# NoMD.net
KiCad netlist of a schematic drawn in EAGLE
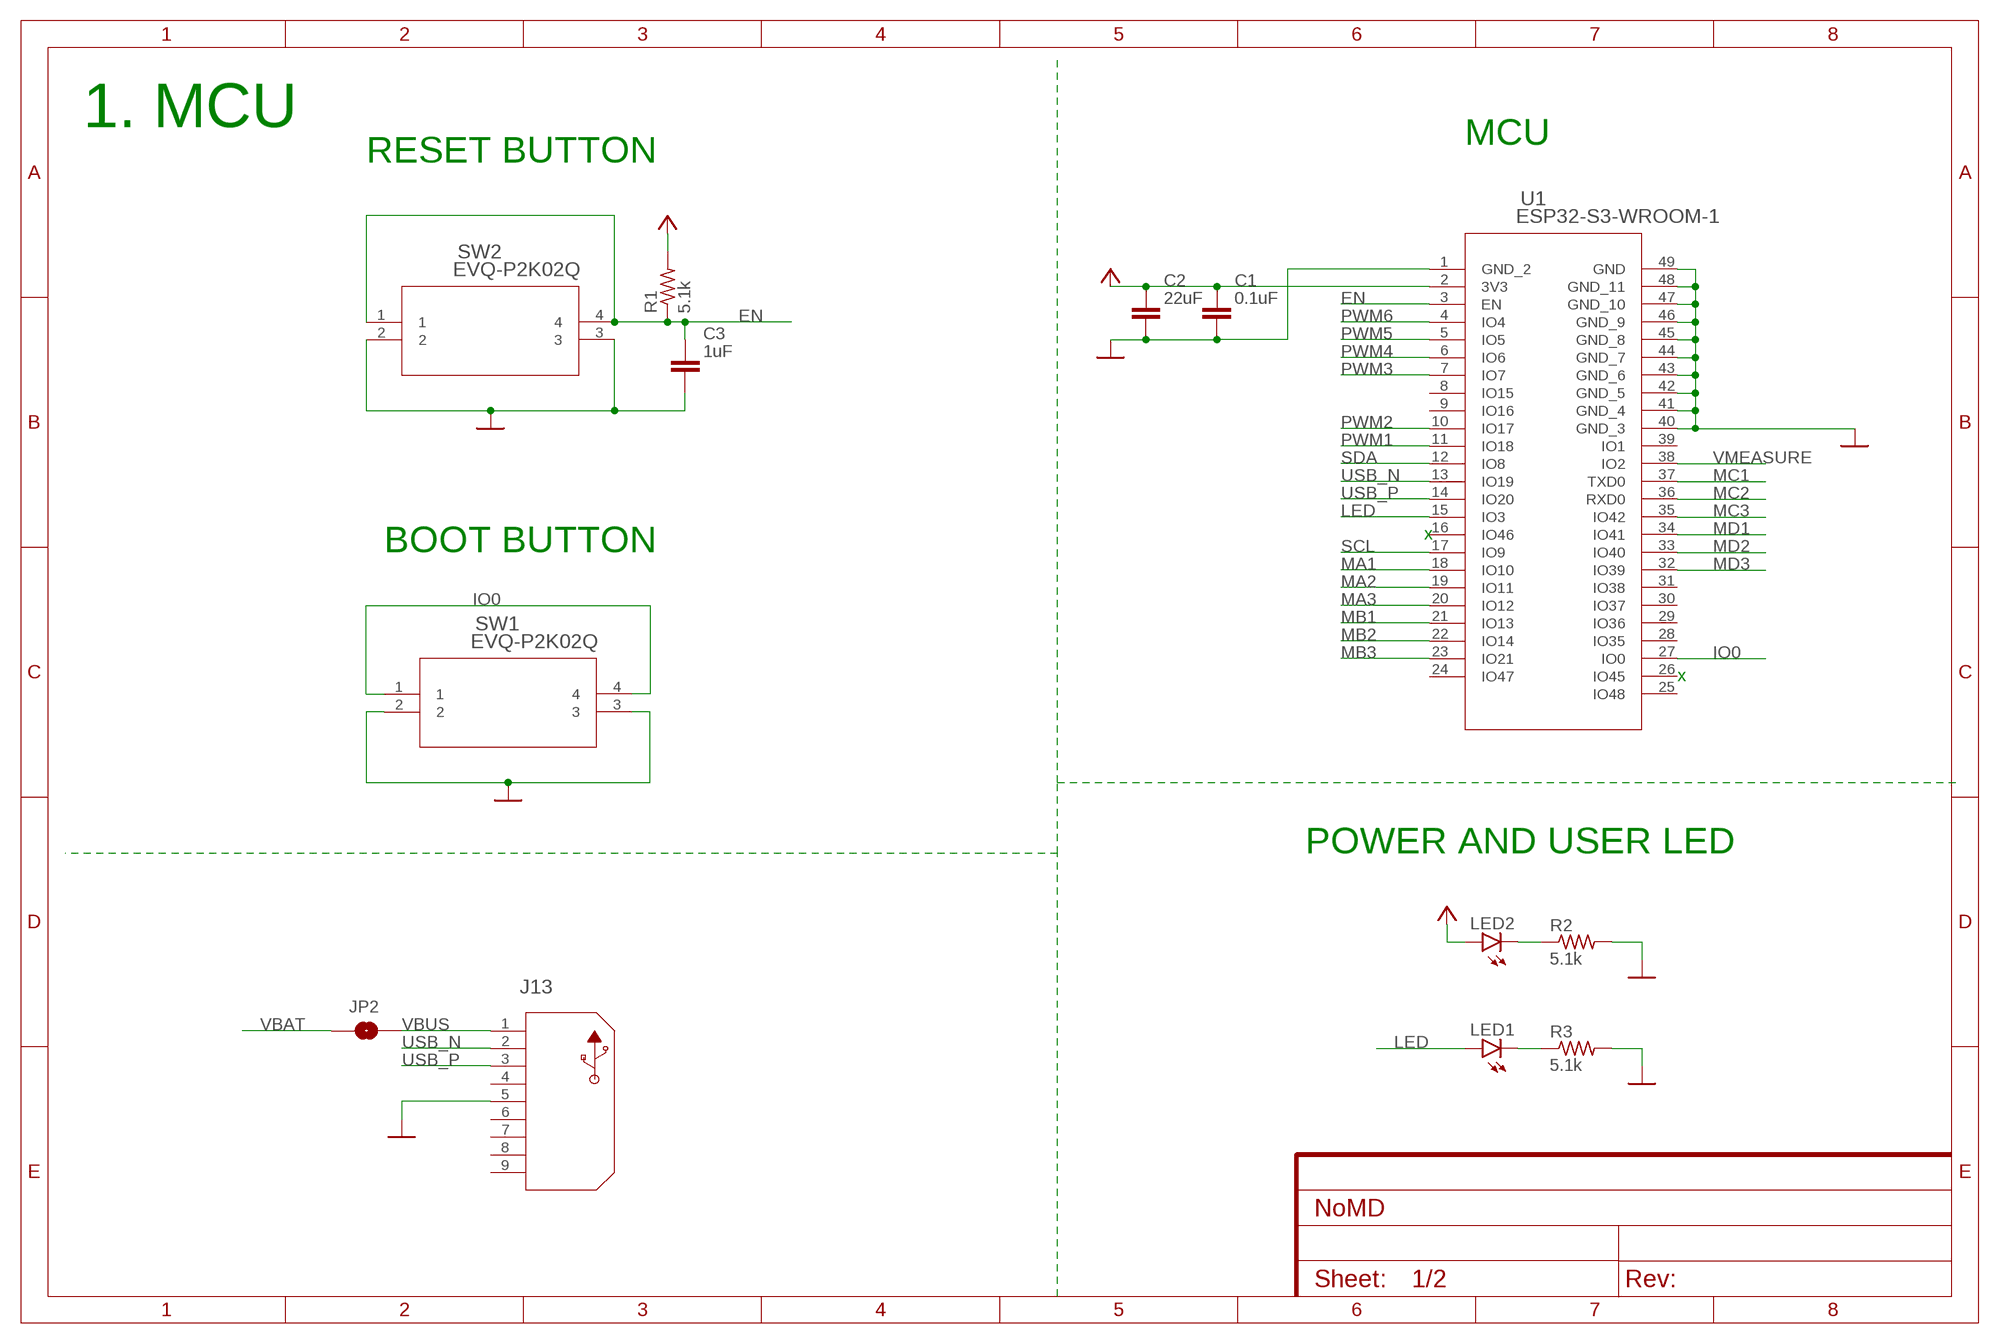
[diagram p0: schematic, sheet 1]
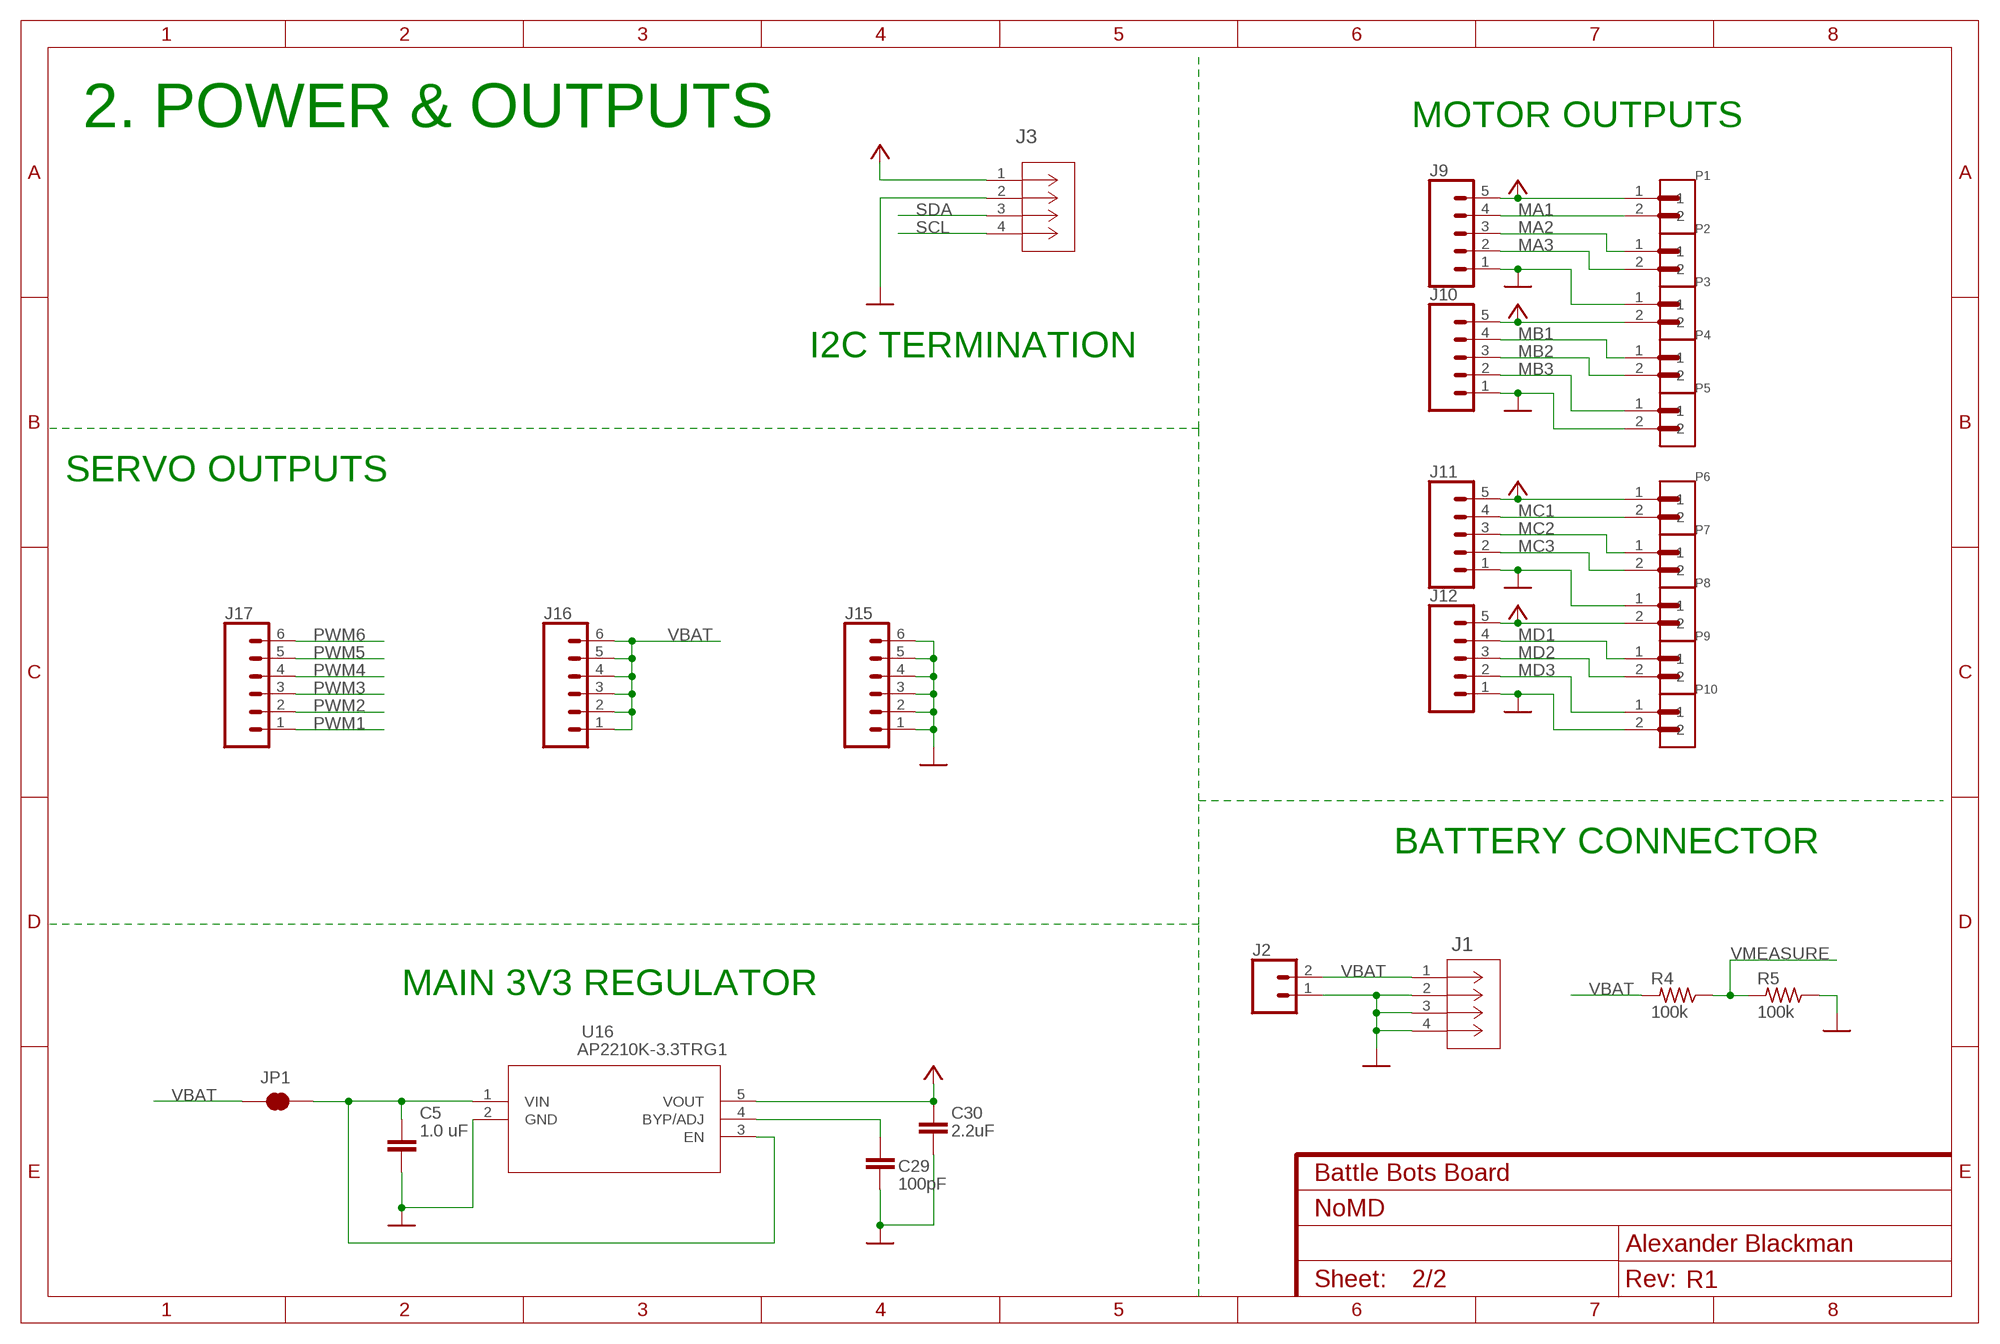
[diagram p1: schematic, sheet 2]

(export (version "E")
  (design (tool "Eeschema 10.0.6"))
  (components
    (comp (ref "C1")
      (value "0.1uF")
      (footprint "eagle-import:CAPC1005X60")
      (libsource (lib "eagle-import") (part "CCHIP-0402(1005-METRIC)_"))
    )
    (comp (ref "C2")
      (value "22uF")
      (footprint "eagle-import:CAPC1005X60")
      (libsource (lib "eagle-import") (part "CCHIP-0402(1005-METRIC)_"))
    )
    (comp (ref "C3")
      (value "1uF")
      (footprint "eagle-import:CAPC1005X60")
      (libsource (lib "eagle-import") (part "CCHIP-0402(1005-METRIC)_"))
    )
    (comp (ref "J13")
      (value "1734035-2")
      (footprint "eagle-import:CONN5_USB1734035_TEC")
      (fields (field (name "COPYRIGHT") "Copyright (C) 2022 Ultra Librarian. All rights reserved."))
      (libsource (lib "eagle-import") (part "1734035-2"))
    )
    (comp (ref "JP2")
      (value "JUMPER-SMT_2_NO_SILK")
      (footprint "eagle-import:SMT-JUMPER_2_NO_SILK")
      (libsource (lib "eagle-import") (part "JUMPER-SMT_2_NO_SILK"))
    )
    (comp (ref "LED1")
      (value "LEDCHIPLED_0603")
      (footprint "eagle-import:CHIPLED_0603")
      (libsource (lib "eagle-import") (part "LEDCHIPLED_0603"))
    )
    (comp (ref "LED2")
      (value "LEDCHIPLED_0603")
      (footprint "eagle-import:CHIPLED_0603")
      (libsource (lib "eagle-import") (part "LEDCHIPLED_0603"))
    )
    (comp (ref "R1")
      (value "5.1k")
      (footprint "eagle-import:R0402")
      (libsource (lib "eagle-import") (part "R-US_R0402"))
    )
    (comp (ref "R2")
      (value "5.1k")
      (footprint "eagle-import:R0402")
      (libsource (lib "eagle-import") (part "R-US_R0402"))
    )
    (comp (ref "R3")
      (value "5.1k")
      (footprint "eagle-import:R0402")
      (libsource (lib "eagle-import") (part "R-US_R0402"))
    )
    (comp (ref "SW1")
      (value "EVQ-P2K02Q")
      (footprint "eagle-import:EVQP2K_PAN")
      (fields (field (name "COPYRIGHT") "Copyright (C) 2022 Ultra Librarian. All rights reserved."))
      (libsource (lib "eagle-import") (part "EVQ-P2K02Q"))
    )
    (comp (ref "SW2")
      (value "EVQ-P2K02Q")
      (footprint "eagle-import:EVQP2K_PAN")
      (fields (field (name "COPYRIGHT") "Copyright (C) 2022 Ultra Librarian. All rights reserved."))
      (libsource (lib "eagle-import") (part "EVQ-P2K02Q"))
    )
    (comp (ref "U1")
      (value "ESP32-S3-WROOM-1")
      (footprint "eagle-import:ESP32-S3-WROOM-1_EXP")
      (fields
        (field (name "MANUFACTURER_PART_NUMBER") "ESP32-S3-WROOM-1-N16R2")
        (field (name "COPYRIGHT") "Copyright (C) 2023 Ultra Librarian. All rights reserved.")
      )
      (libsource (lib "eagle-import") (part "ESP32-S3-WROOM-1-N16R2"))
    )
    (comp (ref "C5")
      (value "1.0 uF")
      (footprint "eagle-import:CAPC1005X60")
      (libsource (lib "eagle-import") (part "CCHIP-0402(1005-METRIC)_"))
    )
    (comp (ref "C29")
      (value "100pF")
      (footprint "eagle-import:CAPC1005X60")
      (libsource (lib "eagle-import") (part "CCHIP-0402(1005-METRIC)_"))
    )
    (comp (ref "C30")
      (value "2.2uF")
      (footprint "eagle-import:CAPC1005X60")
      (libsource (lib "eagle-import") (part "CCHIP-0402(1005-METRIC)_"))
    )
    (comp (ref "J1")
      (value "S2B-PH-SM4-TB(LF)(SN)")
      (footprint "eagle-import:CONN_S2B-PH-SM4-TB_JST")
      (fields (field (name "COPYRIGHT") "Copyright (C) 2022 Ultra Librarian. All rights reserved."))
      (libsource (lib "eagle-import") (part "S2B-PH-SM4-TB(LF)(SN)"))
    )
    (comp (ref "J2")
      (value "CONN_021X02_NO_SILK")
      (footprint "eagle-import:1X02_NO_SILK")
      (libsource (lib "eagle-import") (part "CONN_021X02_NO_SILK"))
    )
    (comp (ref "J3")
      (value "SM04B-SRSS-TB(LF)(SN)")
      (footprint "eagle-import:CONN_SM04B_JST")
      (fields (field (name "COPYRIGHT") "Copyright (C) 2023 Ultra Librarian. All rights reserved."))
      (libsource (lib "eagle-import") (part "SM04B-SRSS-TB(LF)(SN)"))
    )
    (comp (ref "J9")
      (value "CONN_05NO_SILK")
      (footprint "eagle-import:1X05_NO_SILK")
      (libsource (lib "eagle-import") (part "CONN_05NO_SILK"))
    )
    (comp (ref "J10")
      (value "CONN_05NO_SILK")
      (footprint "eagle-import:1X05_NO_SILK")
      (libsource (lib "eagle-import") (part "CONN_05NO_SILK"))
    )
    (comp (ref "J11")
      (value "CONN_05NO_SILK")
      (footprint "eagle-import:1X05_NO_SILK")
      (libsource (lib "eagle-import") (part "CONN_05NO_SILK"))
    )
    (comp (ref "J12")
      (value "CONN_05NO_SILK")
      (footprint "eagle-import:1X05_NO_SILK")
      (libsource (lib "eagle-import") (part "CONN_05NO_SILK"))
    )
    (comp (ref "J15")
      (value "CONN_06NO_SILK_NO_POP")
      (footprint "eagle-import:1X06_NO_SILK")
      (libsource (lib "eagle-import") (part "CONN_06NO_SILK_NO_POP"))
    )
    (comp (ref "J16")
      (value "CONN_06NO_SILK_NO_POP")
      (footprint "eagle-import:1X06_NO_SILK")
      (libsource (lib "eagle-import") (part "CONN_06NO_SILK_NO_POP"))
    )
    (comp (ref "J17")
      (value "CONN_06NO_SILK_NO_POP")
      (footprint "eagle-import:1X06_NO_SILK")
      (libsource (lib "eagle-import") (part "CONN_06NO_SILK_NO_POP"))
    )
    (comp (ref "JP1")
      (value "JUMPER-SMT_2_NC_TRACE_NO-SILK")
      (footprint "eagle-import:SMT-JUMPER_2_NC_TRACE_NO-SILK")
      (libsource (lib "eagle-import") (part "JUMPER-SMT_2_NC_TRACE_NO-SILK"))
    )
    (comp (ref "P1")
      (value "OSTTE020104")
      (footprint "eagle-import:OST_OSTTE020104")
      (fields (field (name "DIGI-KEY_PART_NUMBER") "ED2740-ND") (field (name "MF") "On Shore"))
      (libsource (lib "eagle-import") (part "OSTTE020104"))
    )
    (comp (ref "P2")
      (value "OSTTE020104")
      (footprint "eagle-import:OST_OSTTE020104")
      (fields (field (name "DIGI-KEY_PART_NUMBER") "ED2740-ND") (field (name "MF") "On Shore"))
      (libsource (lib "eagle-import") (part "OSTTE020104"))
    )
    (comp (ref "P3")
      (value "OSTTE020104")
      (footprint "eagle-import:OST_OSTTE020104")
      (fields (field (name "DIGI-KEY_PART_NUMBER") "ED2740-ND") (field (name "MF") "On Shore"))
      (libsource (lib "eagle-import") (part "OSTTE020104"))
    )
    (comp (ref "P4")
      (value "OSTTE020104")
      (footprint "eagle-import:OST_OSTTE020104")
      (fields (field (name "DIGI-KEY_PART_NUMBER") "ED2740-ND") (field (name "MF") "On Shore"))
      (libsource (lib "eagle-import") (part "OSTTE020104"))
    )
    (comp (ref "P5")
      (value "OSTTE020104")
      (footprint "eagle-import:OST_OSTTE020104")
      (fields (field (name "DIGI-KEY_PART_NUMBER") "ED2740-ND") (field (name "MF") "On Shore"))
      (libsource (lib "eagle-import") (part "OSTTE020104"))
    )
    (comp (ref "P6")
      (value "OSTTE020104")
      (footprint "eagle-import:OST_OSTTE020104")
      (fields (field (name "DIGI-KEY_PART_NUMBER") "ED2740-ND") (field (name "MF") "On Shore"))
      (libsource (lib "eagle-import") (part "OSTTE020104"))
    )
    (comp (ref "P7")
      (value "OSTTE020104")
      (footprint "eagle-import:OST_OSTTE020104")
      (fields (field (name "DIGI-KEY_PART_NUMBER") "ED2740-ND") (field (name "MF") "On Shore"))
      (libsource (lib "eagle-import") (part "OSTTE020104"))
    )
    (comp (ref "P8")
      (value "OSTTE020104")
      (footprint "eagle-import:OST_OSTTE020104")
      (fields (field (name "DIGI-KEY_PART_NUMBER") "ED2740-ND") (field (name "MF") "On Shore"))
      (libsource (lib "eagle-import") (part "OSTTE020104"))
    )
    (comp (ref "P9")
      (value "OSTTE020104")
      (footprint "eagle-import:OST_OSTTE020104")
      (fields (field (name "DIGI-KEY_PART_NUMBER") "ED2740-ND") (field (name "MF") "On Shore"))
      (libsource (lib "eagle-import") (part "OSTTE020104"))
    )
    (comp (ref "P10")
      (value "OSTTE020104")
      (footprint "eagle-import:OST_OSTTE020104")
      (fields (field (name "DIGI-KEY_PART_NUMBER") "ED2740-ND") (field (name "MF") "On Shore"))
      (libsource (lib "eagle-import") (part "OSTTE020104"))
    )
    (comp (ref "R4")
      (value "100k")
      (footprint "eagle-import:R0402")
      (libsource (lib "eagle-import") (part "R-US_R0402"))
    )
    (comp (ref "R5")
      (value "100k")
      (footprint "eagle-import:R0402")
      (libsource (lib "eagle-import") (part "R-US_R0402"))
    )
    (comp (ref "U16")
      (value "AP2210K-3.3TRG1")
      (footprint "eagle-import:SOT-23-5_DIO")
      (fields (field (name "COPYRIGHT") "Copyright (C) 2023 Ultra Librarian. All rights reserved."))
      (libsource (lib "eagle-import") (part "AP2210K-3.3TRG1"))
    )
  )
  (nets
    (net (code "1") (name "+3V3") (class "Default")
      (node (ref "C1") (pin "1") (pinfunction "1_1") (pintype "passive"))
      (node (ref "C2") (pin "1") (pinfunction "1_1") (pintype "passive"))
      (node (ref "C30") (pin "1") (pinfunction "1_1") (pintype "passive"))
      (node (ref "J10") (pin "5") (pinfunction "5_5") (pintype "passive"))
      (node (ref "J11") (pin "5") (pinfunction "5_5") (pintype "passive"))
      (node (ref "J12") (pin "5") (pinfunction "5_5") (pintype "passive"))
      (node (ref "J3") (pin "1") (pinfunction "1_1") (pintype "passive"))
      (node (ref "J9") (pin "5") (pinfunction "5_5") (pintype "passive"))
      (node (ref "LED2") (pin "A") (pinfunction "A_A") (pintype "passive"))
      (node (ref "P1") (pin "1") (pinfunction "1_1") (pintype "passive"))
      (node (ref "P3") (pin "2") (pinfunction "2_2") (pintype "passive"))
      (node (ref "P6") (pin "1") (pinfunction "1_1") (pintype "passive"))
      (node (ref "P8") (pin "2") (pinfunction "2_2") (pintype "passive"))
      (node (ref "R1") (pin "2") (pinfunction "2_2") (pintype "passive"))
      (node (ref "U1") (pin "2") (pinfunction "3V3_2") (pintype "power_in"))
      (node (ref "U16") (pin "5") (pinfunction "VOUT_5") (pintype "output"))
    )
    (net (code "2") (name "EN") (class "Default")
      (node (ref "C3") (pin "1") (pinfunction "1_1") (pintype "passive"))
      (node (ref "R1") (pin "1") (pinfunction "1_1") (pintype "passive"))
      (node (ref "SW2") (pin "1") (pinfunction "1_1") (pintype "passive"))
      (node (ref "SW2") (pin "4") (pinfunction "4_4") (pintype "passive"))
      (node (ref "U1") (pin "3") (pinfunction "EN_3") (pintype "input"))
    )
    (net (code "3") (name "GND") (class "Default")
      (node (ref "C1") (pin "2") (pinfunction "2_2") (pintype "passive"))
      (node (ref "C2") (pin "2") (pinfunction "2_2") (pintype "passive"))
      (node (ref "C29") (pin "2") (pinfunction "2_2") (pintype "passive"))
      (node (ref "C3") (pin "2") (pinfunction "2_2") (pintype "passive"))
      (node (ref "C30") (pin "2") (pinfunction "2_2") (pintype "passive"))
      (node (ref "C5") (pin "2") (pinfunction "2_2") (pintype "passive"))
      (node (ref "J1") (pin "2") (pinfunction "2_2") (pintype "passive"))
      (node (ref "J1") (pin "3") (pinfunction "SHIELD_2_3") (pintype "passive"))
      (node (ref "J1") (pin "4") (pinfunction "SHIELD_4") (pintype "passive"))
      (node (ref "J10") (pin "1") (pinfunction "1_1") (pintype "passive"))
      (node (ref "J11") (pin "1") (pinfunction "1_1") (pintype "passive"))
      (node (ref "J12") (pin "1") (pinfunction "1_1") (pintype "passive"))
      (node (ref "J13") (pin "5") (pinfunction "5_5") (pintype "passive"))
      (node (ref "J15") (pin "1") (pinfunction "1_1") (pintype "passive"))
      (node (ref "J15") (pin "2") (pinfunction "2_2") (pintype "passive"))
      (node (ref "J15") (pin "3") (pinfunction "3_3") (pintype "passive"))
      (node (ref "J15") (pin "4") (pinfunction "4_4") (pintype "passive"))
      (node (ref "J15") (pin "5") (pinfunction "5_5") (pintype "passive"))
      (node (ref "J15") (pin "6") (pinfunction "6_6") (pintype "passive"))
      (node (ref "J2") (pin "1") (pinfunction "1_1") (pintype "passive"))
      (node (ref "J3") (pin "2") (pinfunction "2_2") (pintype "passive"))
      (node (ref "J9") (pin "1") (pinfunction "1_1") (pintype "passive"))
      (node (ref "P10") (pin "2") (pinfunction "2_2") (pintype "passive"))
      (node (ref "P3") (pin "1") (pinfunction "1_1") (pintype "passive"))
      (node (ref "P5") (pin "2") (pinfunction "2_2") (pintype "passive"))
      (node (ref "P8") (pin "1") (pinfunction "1_1") (pintype "passive"))
      (node (ref "R2") (pin "2") (pinfunction "2_2") (pintype "passive"))
      (node (ref "R3") (pin "2") (pinfunction "2_2") (pintype "passive"))
      (node (ref "R5") (pin "1") (pinfunction "1_1") (pintype "passive"))
      (node (ref "SW1") (pin "2") (pinfunction "2_2") (pintype "passive"))
      (node (ref "SW1") (pin "3") (pinfunction "3_3") (pintype "passive"))
      (node (ref "SW2") (pin "2") (pinfunction "2_2") (pintype "passive"))
      (node (ref "SW2") (pin "3") (pinfunction "3_3") (pintype "passive"))
      (node (ref "U1") (pin "1") (pinfunction "GND_2_1") (pintype "passive"))
      (node (ref "U1") (pin "40") (pinfunction "GND_3_40") (pintype "passive"))
      (node (ref "U1") (pin "41") (pinfunction "GND_4_41") (pintype "passive"))
      (node (ref "U1") (pin "42") (pinfunction "GND_5_42") (pintype "passive"))
      (node (ref "U1") (pin "43") (pinfunction "GND_6_43") (pintype "passive"))
      (node (ref "U1") (pin "44") (pinfunction "GND_7_44") (pintype "passive"))
      (node (ref "U1") (pin "45") (pinfunction "GND_8_45") (pintype "passive"))
      (node (ref "U1") (pin "46") (pinfunction "GND_9_46") (pintype "passive"))
      (node (ref "U1") (pin "47") (pinfunction "GND_10_47") (pintype "passive"))
      (node (ref "U1") (pin "48") (pinfunction "GND_11_48") (pintype "passive"))
      (node (ref "U1") (pin "49") (pinfunction "GND_49") (pintype "passive"))
      (node (ref "U16") (pin "2") (pinfunction "GND_2") (pintype "passive"))
    )
    (net (code "4") (name "IO0") (class "Default")
      (node (ref "SW1") (pin "1") (pinfunction "1_1") (pintype "passive"))
      (node (ref "SW1") (pin "4") (pinfunction "4_4") (pintype "passive"))
      (node (ref "U1") (pin "27") (pinfunction "IO0_27") (pintype "bidirectional"))
    )
    (net (code "5") (name "LED") (class "Default")
      (node (ref "LED1") (pin "A") (pinfunction "A_A") (pintype "passive"))
      (node (ref "U1") (pin "15") (pinfunction "IO3_15") (pintype "bidirectional"))
    )
    (net (code "6") (name "MA1") (class "Default")
      (node (ref "J9") (pin "4") (pinfunction "4_4") (pintype "passive"))
      (node (ref "P1") (pin "2") (pinfunction "2_2") (pintype "passive"))
      (node (ref "U1") (pin "18") (pinfunction "IO10_18") (pintype "bidirectional"))
    )
    (net (code "7") (name "MA2") (class "Default")
      (node (ref "J9") (pin "3") (pinfunction "3_3") (pintype "passive"))
      (node (ref "P2") (pin "1") (pinfunction "1_1") (pintype "passive"))
      (node (ref "U1") (pin "19") (pinfunction "IO11_19") (pintype "bidirectional"))
    )
    (net (code "8") (name "MA3") (class "Default")
      (node (ref "J9") (pin "2") (pinfunction "2_2") (pintype "passive"))
      (node (ref "P2") (pin "2") (pinfunction "2_2") (pintype "passive"))
      (node (ref "U1") (pin "20") (pinfunction "IO12_20") (pintype "bidirectional"))
    )
    (net (code "9") (name "MB1") (class "Default")
      (node (ref "J10") (pin "4") (pinfunction "4_4") (pintype "passive"))
      (node (ref "P4") (pin "1") (pinfunction "1_1") (pintype "passive"))
      (node (ref "U1") (pin "21") (pinfunction "IO13_21") (pintype "bidirectional"))
    )
    (net (code "10") (name "MB2") (class "Default")
      (node (ref "J10") (pin "3") (pinfunction "3_3") (pintype "passive"))
      (node (ref "P4") (pin "2") (pinfunction "2_2") (pintype "passive"))
      (node (ref "U1") (pin "22") (pinfunction "IO14_22") (pintype "bidirectional"))
    )
    (net (code "11") (name "MB3") (class "Default")
      (node (ref "J10") (pin "2") (pinfunction "2_2") (pintype "passive"))
      (node (ref "P5") (pin "1") (pinfunction "1_1") (pintype "passive"))
      (node (ref "U1") (pin "23") (pinfunction "IO21_23") (pintype "bidirectional"))
    )
    (net (code "12") (name "MC1") (class "Default")
      (node (ref "J11") (pin "4") (pinfunction "4_4") (pintype "passive"))
      (node (ref "P6") (pin "2") (pinfunction "2_2") (pintype "passive"))
      (node (ref "U1") (pin "37") (pinfunction "TXD0_37") (pintype "bidirectional"))
    )
    (net (code "13") (name "MC2") (class "Default")
      (node (ref "J11") (pin "3") (pinfunction "3_3") (pintype "passive"))
      (node (ref "P7") (pin "1") (pinfunction "1_1") (pintype "passive"))
      (node (ref "U1") (pin "36") (pinfunction "RXD0_36") (pintype "bidirectional"))
    )
    (net (code "14") (name "MC3") (class "Default")
      (node (ref "J11") (pin "2") (pinfunction "2_2") (pintype "passive"))
      (node (ref "P7") (pin "2") (pinfunction "2_2") (pintype "passive"))
      (node (ref "U1") (pin "35") (pinfunction "IO42_35") (pintype "bidirectional"))
    )
    (net (code "15") (name "MD1") (class "Default")
      (node (ref "J12") (pin "4") (pinfunction "4_4") (pintype "passive"))
      (node (ref "P9") (pin "1") (pinfunction "1_1") (pintype "passive"))
      (node (ref "U1") (pin "34") (pinfunction "IO41_34") (pintype "bidirectional"))
    )
    (net (code "16") (name "MD2") (class "Default")
      (node (ref "J12") (pin "3") (pinfunction "3_3") (pintype "passive"))
      (node (ref "P9") (pin "2") (pinfunction "2_2") (pintype "passive"))
      (node (ref "U1") (pin "33") (pinfunction "IO40_33") (pintype "bidirectional"))
    )
    (net (code "17") (name "MD3") (class "Default")
      (node (ref "J12") (pin "2") (pinfunction "2_2") (pintype "passive"))
      (node (ref "P10") (pin "1") (pinfunction "1_1") (pintype "passive"))
      (node (ref "U1") (pin "32") (pinfunction "IO39_32") (pintype "bidirectional"))
    )
    (net (code "18") (name "Net-(LED1-PadC)") (class "Default")
      (node (ref "LED1") (pin "C") (pinfunction "C_C") (pintype "passive"))
      (node (ref "R3") (pin "1") (pinfunction "1_1") (pintype "passive"))
    )
    (net (code "19") (name "Net-(LED2-PadC)") (class "Default")
      (node (ref "LED2") (pin "C") (pinfunction "C_C") (pintype "passive"))
      (node (ref "R2") (pin "1") (pinfunction "1_1") (pintype "passive"))
    )
    (net (code "20") (name "Net-(U16-BYP{slash}ADJ)") (class "Default")
      (node (ref "C29") (pin "1") (pinfunction "1_1") (pintype "passive"))
      (node (ref "U16") (pin "4") (pinfunction "BYP/ADJ_4") (pintype "output"))
    )
    (net (code "21") (name "PWM1") (class "Default")
      (node (ref "J17") (pin "1") (pinfunction "1_1") (pintype "passive"))
      (node (ref "U1") (pin "11") (pinfunction "IO18_11") (pintype "bidirectional"))
    )
    (net (code "22") (name "PWM2") (class "Default")
      (node (ref "J17") (pin "2") (pinfunction "2_2") (pintype "passive"))
      (node (ref "U1") (pin "10") (pinfunction "IO17_10") (pintype "bidirectional"))
    )
    (net (code "23") (name "PWM3") (class "Default")
      (node (ref "J17") (pin "3") (pinfunction "3_3") (pintype "passive"))
      (node (ref "U1") (pin "7") (pinfunction "IO7_7") (pintype "bidirectional"))
    )
    (net (code "24") (name "PWM4") (class "Default")
      (node (ref "J17") (pin "4") (pinfunction "4_4") (pintype "passive"))
      (node (ref "U1") (pin "6") (pinfunction "IO6_6") (pintype "bidirectional"))
    )
    (net (code "25") (name "PWM5") (class "Default")
      (node (ref "J17") (pin "5") (pinfunction "5_5") (pintype "passive"))
      (node (ref "U1") (pin "5") (pinfunction "IO5_5") (pintype "bidirectional"))
    )
    (net (code "26") (name "PWM6") (class "Default")
      (node (ref "J17") (pin "6") (pinfunction "6_6") (pintype "passive"))
      (node (ref "U1") (pin "4") (pinfunction "IO4_4") (pintype "bidirectional"))
    )
    (net (code "27") (name "SCL") (class "Default")
      (node (ref "J3") (pin "4") (pinfunction "4_4") (pintype "passive"))
      (node (ref "U1") (pin "17") (pinfunction "IO9_17") (pintype "bidirectional"))
    )
    (net (code "28") (name "SDA") (class "Default")
      (node (ref "J3") (pin "3") (pinfunction "3_3") (pintype "passive"))
      (node (ref "U1") (pin "12") (pinfunction "IO8_12") (pintype "bidirectional"))
    )
    (net (code "29") (name "USB_N") (class "Default")
      (node (ref "J13") (pin "2") (pinfunction "2_2") (pintype "passive"))
      (node (ref "U1") (pin "13") (pinfunction "IO19_13") (pintype "bidirectional"))
    )
    (net (code "30") (name "USB_P") (class "Default")
      (node (ref "J13") (pin "3") (pinfunction "3_3") (pintype "passive"))
      (node (ref "U1") (pin "14") (pinfunction "IO20_14") (pintype "bidirectional"))
    )
    (net (code "31") (name "VBAT") (class "Default")
      (node (ref "C5") (pin "1") (pinfunction "1_1") (pintype "passive"))
      (node (ref "J1") (pin "1") (pinfunction "1_1") (pintype "passive"))
      (node (ref "J16") (pin "1") (pinfunction "1_1") (pintype "passive"))
      (node (ref "J16") (pin "2") (pinfunction "2_2") (pintype "passive"))
      (node (ref "J16") (pin "3") (pinfunction "3_3") (pintype "passive"))
      (node (ref "J16") (pin "4") (pinfunction "4_4") (pintype "passive"))
      (node (ref "J16") (pin "5") (pinfunction "5_5") (pintype "passive"))
      (node (ref "J16") (pin "6") (pinfunction "6_6") (pintype "passive"))
      (node (ref "J2") (pin "2") (pinfunction "2_2") (pintype "passive"))
      (node (ref "JP1") (pin "1") (pinfunction "1_1") (pintype "passive"))
      (node (ref "JP1") (pin "2") (pinfunction "2_2") (pintype "passive"))
      (node (ref "JP2") (pin "1") (pinfunction "1_1") (pintype "passive"))
      (node (ref "R4") (pin "2") (pinfunction "2_2") (pintype "passive"))
      (node (ref "U16") (pin "1") (pinfunction "VIN_1") (pintype "power_in"))
      (node (ref "U16") (pin "3") (pinfunction "EN_3") (pintype "input"))
    )
    (net (code "32") (name "VBUS") (class "Default")
      (node (ref "J13") (pin "1") (pinfunction "1_1") (pintype "passive"))
      (node (ref "JP2") (pin "2") (pinfunction "2_2") (pintype "passive"))
    )
    (net (code "33") (name "VMEASURE") (class "Default")
      (node (ref "R4") (pin "1") (pinfunction "1_1") (pintype "passive"))
      (node (ref "R5") (pin "2") (pinfunction "2_2") (pintype "passive"))
      (node (ref "U1") (pin "38") (pinfunction "IO2_38") (pintype "bidirectional"))
    )
    (net (code "34") (name "unconnected-(J13-Pad4)") (class "Default")
      (node (ref "J13") (pin "4") (pinfunction "4_4") (pintype "passive"))
    )
    (net (code "35") (name "unconnected-(J13-Pad6)") (class "Default")
      (node (ref "J13") (pin "6") (pinfunction "6_6") (pintype "passive"))
    )
    (net (code "36") (name "unconnected-(J13-Pad7)") (class "Default")
      (node (ref "J13") (pin "7") (pinfunction "7_7") (pintype "passive"))
    )
    (net (code "37") (name "unconnected-(J13-Pad8)") (class "Default")
      (node (ref "J13") (pin "8") (pinfunction "8_8") (pintype "passive"))
    )
    (net (code "38") (name "unconnected-(J13-Pad9)") (class "Default")
      (node (ref "J13") (pin "9") (pinfunction "9_9") (pintype "passive"))
    )
    (net (code "39") (name "unconnected-(U1-IO1-Pad39)") (class "Default")
      (node (ref "U1") (pin "39") (pinfunction "IO1_39") (pintype "bidirectional"))
    )
    (net (code "40") (name "unconnected-(U1-IO15-Pad8)") (class "Default")
      (node (ref "U1") (pin "8") (pinfunction "IO15_8") (pintype "bidirectional"))
    )
    (net (code "41") (name "unconnected-(U1-IO16-Pad9)") (class "Default")
      (node (ref "U1") (pin "9") (pinfunction "IO16_9") (pintype "bidirectional"))
    )
    (net (code "42") (name "unconnected-(U1-IO35-Pad28)") (class "Default")
      (node (ref "U1") (pin "28") (pinfunction "IO35_28") (pintype "bidirectional"))
    )
    (net (code "43") (name "unconnected-(U1-IO36-Pad29)") (class "Default")
      (node (ref "U1") (pin "29") (pinfunction "IO36_29") (pintype "bidirectional"))
    )
    (net (code "44") (name "unconnected-(U1-IO37-Pad30)") (class "Default")
      (node (ref "U1") (pin "30") (pinfunction "IO37_30") (pintype "bidirectional"))
    )
    (net (code "45") (name "unconnected-(U1-IO38-Pad31)") (class "Default")
      (node (ref "U1") (pin "31") (pinfunction "IO38_31") (pintype "bidirectional"))
    )
    (net (code "46") (name "unconnected-(U1-IO45-Pad26)") (class "Default")
      (node (ref "U1") (pin "26") (pinfunction "IO45_26") (pintype "bidirectional"))
    )
    (net (code "47") (name "unconnected-(U1-IO46-Pad16)") (class "Default")
      (node (ref "U1") (pin "16") (pinfunction "IO46_16") (pintype "bidirectional"))
    )
    (net (code "48") (name "unconnected-(U1-IO47-Pad24)") (class "Default")
      (node (ref "U1") (pin "24") (pinfunction "IO47_24") (pintype "bidirectional"))
    )
    (net (code "49") (name "unconnected-(U1-IO48-Pad25)") (class "Default")
      (node (ref "U1") (pin "25") (pinfunction "IO48_25") (pintype "bidirectional"))
    )
  )
)
